# Preamp.net
KiCad netlist of a schematic drawn in Altium Designer
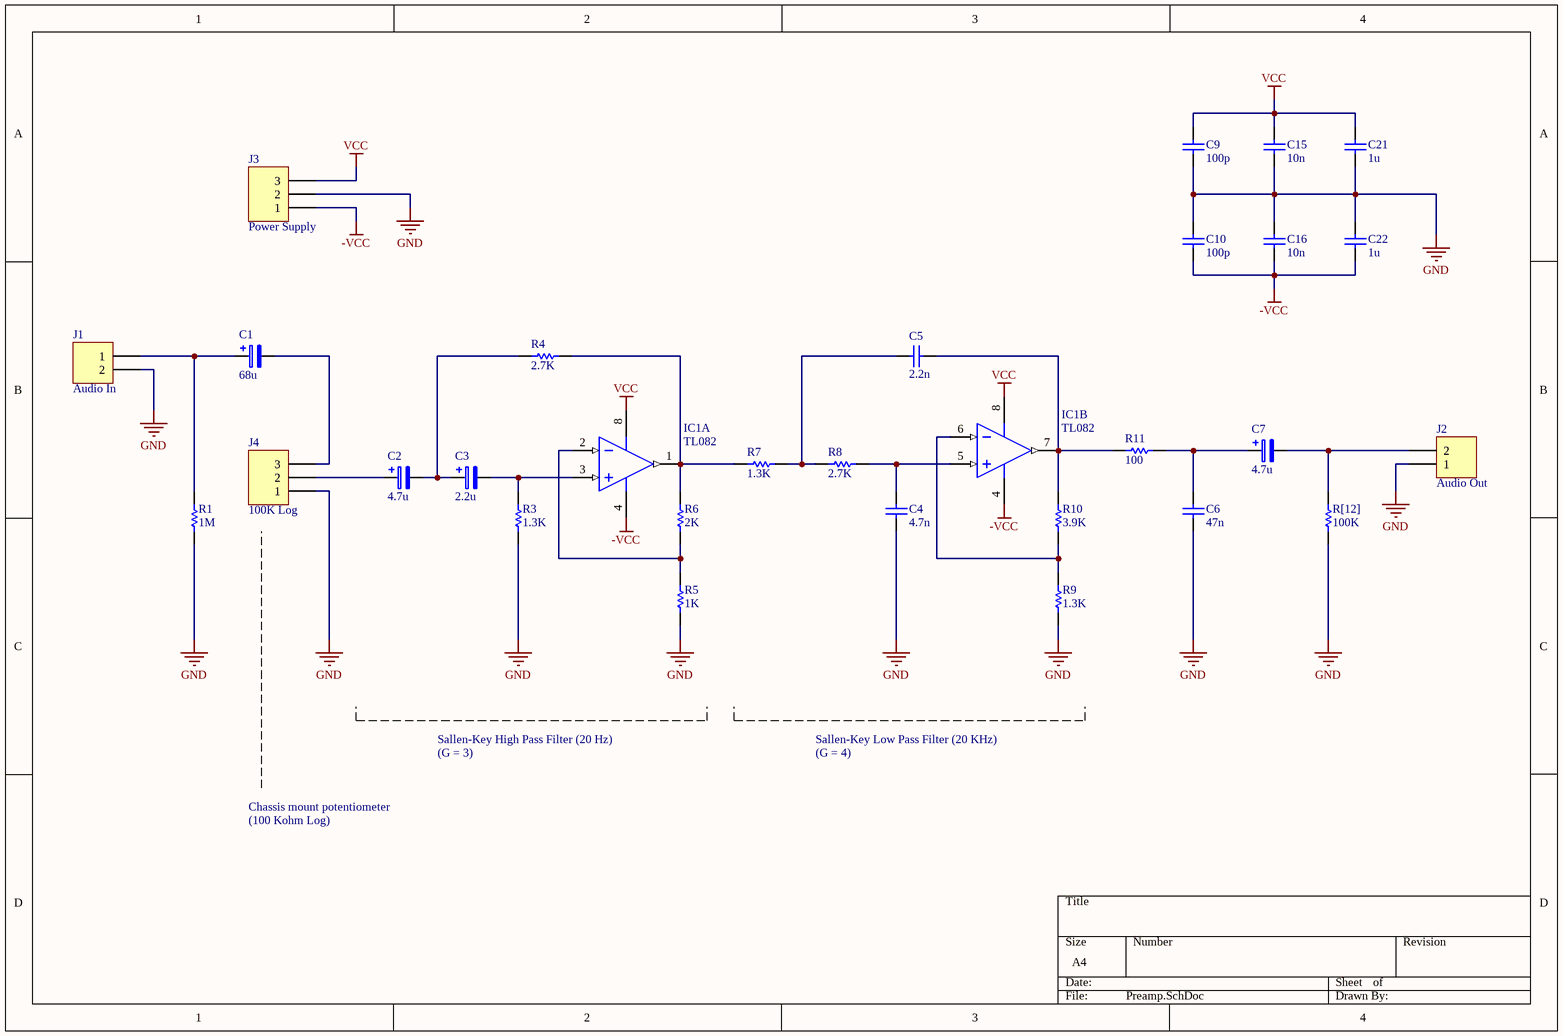
[diagram p0: Preamp.SchDoc]

(export (version "E")
  (design (tool "Eeschema 10.0.6"))
  (components
    (comp (ref "C1")
      (value "68u")
      (footprint "CRADIAL-2.5mm")
      (description "Polarized Capacitor")
      (libsource (lib "nucleoduro_lib_audio") (part "Pol Capacitor"))
    )
    (comp (ref "C2")
      (value "4.7u")
      (footprint "CRADIAL-2mm")
      (description "Polarized Capacitor")
      (libsource (lib "nucleoduro_lib_audio") (part "Pol Capacitor"))
    )
    (comp (ref "C3")
      (value "2.2u")
      (footprint "CRADIAL-2mm")
      (description "Polarized Capacitor")
      (libsource (lib "nucleoduro_lib_audio") (part "Pol Capacitor"))
    )
    (comp (ref "C4")
      (value "4.7n")
      (footprint "C0805")
      (description "Capacitor")
      (libsource (lib "nucleoduro_lib_audio") (part "Capacitor"))
    )
    (comp (ref "C5")
      (value "2.2n")
      (footprint "C0805")
      (description "Capacitor")
      (libsource (lib "nucleoduro_lib_audio") (part "Capacitor"))
    )
    (comp (ref "C6")
      (value "47n")
      (footprint "C1206")
      (description "Capacitor")
      (libsource (lib "nucleoduro_lib_audio") (part "Capacitor"))
    )
    (comp (ref "C7")
      (value "4.7u")
      (footprint "CRADIAL-2mm")
      (description "Polarized Capacitor")
      (libsource (lib "nucleoduro_lib_audio") (part "Pol Capacitor"))
    )
    (comp (ref "C9")
      (value "100p")
      (footprint "C0805")
      (description "Capacitor")
      (libsource (lib "nucleoduro_lib_audio") (part "Capacitor"))
    )
    (comp (ref "C10")
      (value "100p")
      (footprint "C0805")
      (description "Capacitor")
      (libsource (lib "nucleoduro_lib_audio") (part "Capacitor"))
    )
    (comp (ref "C15")
      (value "10n")
      (footprint "C0805")
      (description "Capacitor")
      (libsource (lib "nucleoduro_lib_audio") (part "Capacitor"))
    )
    (comp (ref "C16")
      (value "10n")
      (footprint "C0805")
      (description "Capacitor")
      (libsource (lib "nucleoduro_lib_audio") (part "Capacitor"))
    )
    (comp (ref "C21")
      (value "1u")
      (footprint "C0805")
      (description "Capacitor")
      (libsource (lib "nucleoduro_lib_audio") (part "Capacitor"))
    )
    (comp (ref "C22")
      (value "1u")
      (footprint "C0805")
      (description "Capacitor")
      (libsource (lib "nucleoduro_lib_audio") (part "Capacitor"))
    )
    (comp (ref "IC1")
      (value "TL082")
      (footprint "SOIC127P600X175-8N")
      (libsource (lib "nucleoduro_lib_audio") (part "TL082"))
    )
    (comp (ref "J1")
      (value "Audio In")
      (footprint "2 Pin 5mm Terminal Block")
      (description "Terminal Block, 2 Pin")
      (libsource (lib "") (part "Terminal Block 2 Pin_1"))
    )
    (comp (ref "J2")
      (value "Audio Out")
      (footprint "2 Pin 5mm Terminal Block")
      (description "Terminal Block, 2 Pin")
      (libsource (lib "nucleoduro_lib_audio") (part "Terminal Block 2 Pin"))
    )
    (comp (ref "J3")
      (value "Power Supply")
      (footprint "3 Pin 5mm Terminal Block")
      (description "Terminal Block, 3 Pin")
      (libsource (lib "nucleoduro_lib_audio") (part "Terminal Block 3 Pin"))
    )
    (comp (ref "J4")
      (value "100K Log")
      (footprint "3 Pin 5mm Terminal Block")
      (description "Terminal Block, 3 Pin")
      (libsource (lib "nucleoduro_lib_audio") (part "Terminal Block 3 Pin"))
    )
    (comp (ref "R1")
      (value "1M")
      (footprint "R0805")
      (description "Resistor")
      (libsource (lib "nucleoduro_lib_audio") (part "Resistor"))
    )
    (comp (ref "R3")
      (value "1.3K")
      (footprint "R0805")
      (description "Resistor")
      (libsource (lib "nucleoduro_lib_audio") (part "Resistor"))
    )
    (comp (ref "R4")
      (value "2.7K")
      (footprint "R0805")
      (description "Resistor")
      (libsource (lib "nucleoduro_lib_audio") (part "Resistor"))
    )
    (comp (ref "R5")
      (value "1K")
      (footprint "R0805")
      (description "Resistor")
      (libsource (lib "nucleoduro_lib_audio") (part "Resistor"))
    )
    (comp (ref "R6")
      (value "2K")
      (footprint "R0805")
      (description "Resistor")
      (libsource (lib "nucleoduro_lib_audio") (part "Resistor"))
    )
    (comp (ref "R7")
      (value "1.3K")
      (footprint "R0805")
      (description "Resistor")
      (libsource (lib "nucleoduro_lib_audio") (part "Resistor"))
    )
    (comp (ref "R8")
      (value "2.7K")
      (footprint "R0805")
      (description "Resistor")
      (libsource (lib "nucleoduro_lib_audio") (part "Resistor"))
    )
    (comp (ref "R9")
      (value "1.3K")
      (footprint "R0805")
      (description "Resistor")
      (libsource (lib "nucleoduro_lib_audio") (part "Resistor"))
    )
    (comp (ref "R10")
      (value "3.9K")
      (footprint "R0805")
      (description "Resistor")
      (libsource (lib "nucleoduro_lib_audio") (part "Resistor"))
    )
    (comp (ref "R11")
      (value "100")
      (footprint "R0805")
      (description "Resistor")
      (libsource (lib "nucleoduro_lib_audio") (part "Resistor"))
    )
    (comp (ref "R[12]")
      (value "100K")
      (footprint "R0805")
      (description "Resistor")
      (libsource (lib "nucleoduro_lib_audio") (part "Resistor"))
    )
  )
  (nets
    (net (code "1") (name "-VCC") (class "Default")
      (node (ref "C10") (pin "1") (pinfunction "1_1") (pintype "passive"))
      (node (ref "C16") (pin "1") (pinfunction "1_1") (pintype "passive"))
      (node (ref "C22") (pin "1") (pinfunction "1_1") (pintype "passive"))
      (node (ref "IC1") (pin "4") (pinfunction "V-_4") (pintype "power_in"))
      (node (ref "J3") (pin "1") (pinfunction "1_1") (pintype "passive"))
    )
    (net (code "2") (name "GND") (class "Default")
      (node (ref "C10") (pin "2") (pinfunction "2_2") (pintype "passive"))
      (node (ref "C15") (pin "1") (pinfunction "1_1") (pintype "passive"))
      (node (ref "C16") (pin "2") (pinfunction "2_2") (pintype "passive"))
      (node (ref "C21") (pin "1") (pinfunction "1_1") (pintype "passive"))
      (node (ref "C22") (pin "2") (pinfunction "2_2") (pintype "passive"))
      (node (ref "C4") (pin "1") (pinfunction "1_1") (pintype "passive"))
      (node (ref "C6") (pin "1") (pinfunction "1_1") (pintype "passive"))
      (node (ref "C9") (pin "1") (pinfunction "1_1") (pintype "passive"))
      (node (ref "J1") (pin "2") (pinfunction "2_2") (pintype "passive"))
      (node (ref "J2") (pin "1") (pinfunction "1_1") (pintype "passive"))
      (node (ref "J3") (pin "2") (pinfunction "2_2") (pintype "passive"))
      (node (ref "J4") (pin "1") (pinfunction "1_1") (pintype "passive"))
      (node (ref "R1") (pin "1") (pinfunction "1_1") (pintype "passive"))
      (node (ref "R3") (pin "1") (pinfunction "1_1") (pintype "passive"))
      (node (ref "R5") (pin "2") (pinfunction "2_2") (pintype "passive"))
      (node (ref "R9") (pin "1") (pinfunction "1_1") (pintype "passive"))
      (node (ref "R[12]") (pin "2") (pinfunction "2_2") (pintype "passive"))
    )
    (net (code "3") (name "Net-(C1-Pad1)") (class "Default")
      (node (ref "C1") (pin "1") (pinfunction "1_1") (pintype "passive"))
      (node (ref "J1") (pin "1") (pinfunction "1_1") (pintype "passive"))
      (node (ref "R1") (pin "2") (pinfunction "2_2") (pintype "passive"))
    )
    (net (code "4") (name "Net-(C1-Pad2)") (class "Default")
      (node (ref "C1") (pin "2") (pinfunction "2_2") (pintype "passive"))
      (node (ref "J4") (pin "3") (pinfunction "3_3") (pintype "passive"))
    )
    (net (code "5") (name "Net-(C2-Pad1)") (class "Default")
      (node (ref "C2") (pin "1") (pinfunction "1_1") (pintype "passive"))
      (node (ref "J4") (pin "2") (pinfunction "2_2") (pintype "passive"))
    )
    (net (code "6") (name "Net-(C2-Pad2)") (class "Default")
      (node (ref "C2") (pin "2") (pinfunction "2_2") (pintype "passive"))
      (node (ref "C3") (pin "1") (pinfunction "1_1") (pintype "passive"))
      (node (ref "R4") (pin "2") (pinfunction "2_2") (pintype "passive"))
    )
    (net (code "7") (name "Net-(C5-Pad2)") (class "Default")
      (node (ref "C5") (pin "2") (pinfunction "2_2") (pintype "passive"))
      (node (ref "R7") (pin "2") (pinfunction "2_2") (pintype "passive"))
      (node (ref "R8") (pin "1") (pinfunction "1_1") (pintype "passive"))
    )
    (net (code "8") (name "Net-(C6-Pad2)") (class "Default")
      (node (ref "C6") (pin "2") (pinfunction "2_2") (pintype "passive"))
      (node (ref "C7") (pin "1") (pinfunction "1_1") (pintype "passive"))
      (node (ref "R11") (pin "1") (pinfunction "1_1") (pintype "passive"))
    )
    (net (code "9") (name "Net-(C7-Pad2)") (class "Default")
      (node (ref "C7") (pin "2") (pinfunction "2_2") (pintype "passive"))
      (node (ref "J2") (pin "2") (pinfunction "2_2") (pintype "passive"))
      (node (ref "R[12]") (pin "1") (pinfunction "1_1") (pintype "passive"))
    )
    (net (code "10") (name "Net-(IC1A-IN+1)") (class "Default")
      (node (ref "C3") (pin "2") (pinfunction "2_2") (pintype "passive"))
      (node (ref "IC1") (pin "3") (pinfunction "IN+1_3") (pintype "input"))
      (node (ref "R3") (pin "2") (pinfunction "2_2") (pintype "passive"))
    )
    (net (code "11") (name "Net-(IC1A-IN-1)") (class "Default")
      (node (ref "IC1") (pin "2") (pinfunction "IN-1_2") (pintype "input"))
      (node (ref "R5") (pin "1") (pinfunction "1_1") (pintype "passive"))
      (node (ref "R6") (pin "2") (pinfunction "2_2") (pintype "passive"))
    )
    (net (code "12") (name "Net-(IC1A-OUT1)") (class "Default")
      (node (ref "IC1") (pin "1") (pinfunction "OUT1_1") (pintype "output"))
      (node (ref "R4") (pin "1") (pinfunction "1_1") (pintype "passive"))
      (node (ref "R6") (pin "1") (pinfunction "1_1") (pintype "passive"))
      (node (ref "R7") (pin "1") (pinfunction "1_1") (pintype "passive"))
    )
    (net (code "13") (name "Net-(IC1B-IN+2)") (class "Default")
      (node (ref "C4") (pin "2") (pinfunction "2_2") (pintype "passive"))
      (node (ref "IC1") (pin "5") (pinfunction "IN+2_5") (pintype "input"))
      (node (ref "R8") (pin "2") (pinfunction "2_2") (pintype "passive"))
    )
    (net (code "14") (name "Net-(IC1B-IN-2)") (class "Default")
      (node (ref "IC1") (pin "6") (pinfunction "IN-2_6") (pintype "input"))
      (node (ref "R10") (pin "1") (pinfunction "1_1") (pintype "passive"))
      (node (ref "R9") (pin "2") (pinfunction "2_2") (pintype "passive"))
    )
    (net (code "15") (name "Net-(IC1B-OUT2)") (class "Default")
      (node (ref "C5") (pin "1") (pinfunction "1_1") (pintype "passive"))
      (node (ref "IC1") (pin "7") (pinfunction "OUT2_7") (pintype "output"))
      (node (ref "R10") (pin "2") (pinfunction "2_2") (pintype "passive"))
      (node (ref "R11") (pin "2") (pinfunction "2_2") (pintype "passive"))
    )
    (net (code "16") (name "VCC") (class "Default")
      (node (ref "C15") (pin "2") (pinfunction "2_2") (pintype "passive"))
      (node (ref "C21") (pin "2") (pinfunction "2_2") (pintype "passive"))
      (node (ref "C9") (pin "2") (pinfunction "2_2") (pintype "passive"))
      (node (ref "IC1") (pin "8") (pinfunction "V+_8") (pintype "power_in"))
      (node (ref "J3") (pin "3") (pinfunction "3_3") (pintype "passive"))
    )
  )
)
